# os_-_5V0_converter.net
KiCad netlist of a schematic drawn in EAGLE
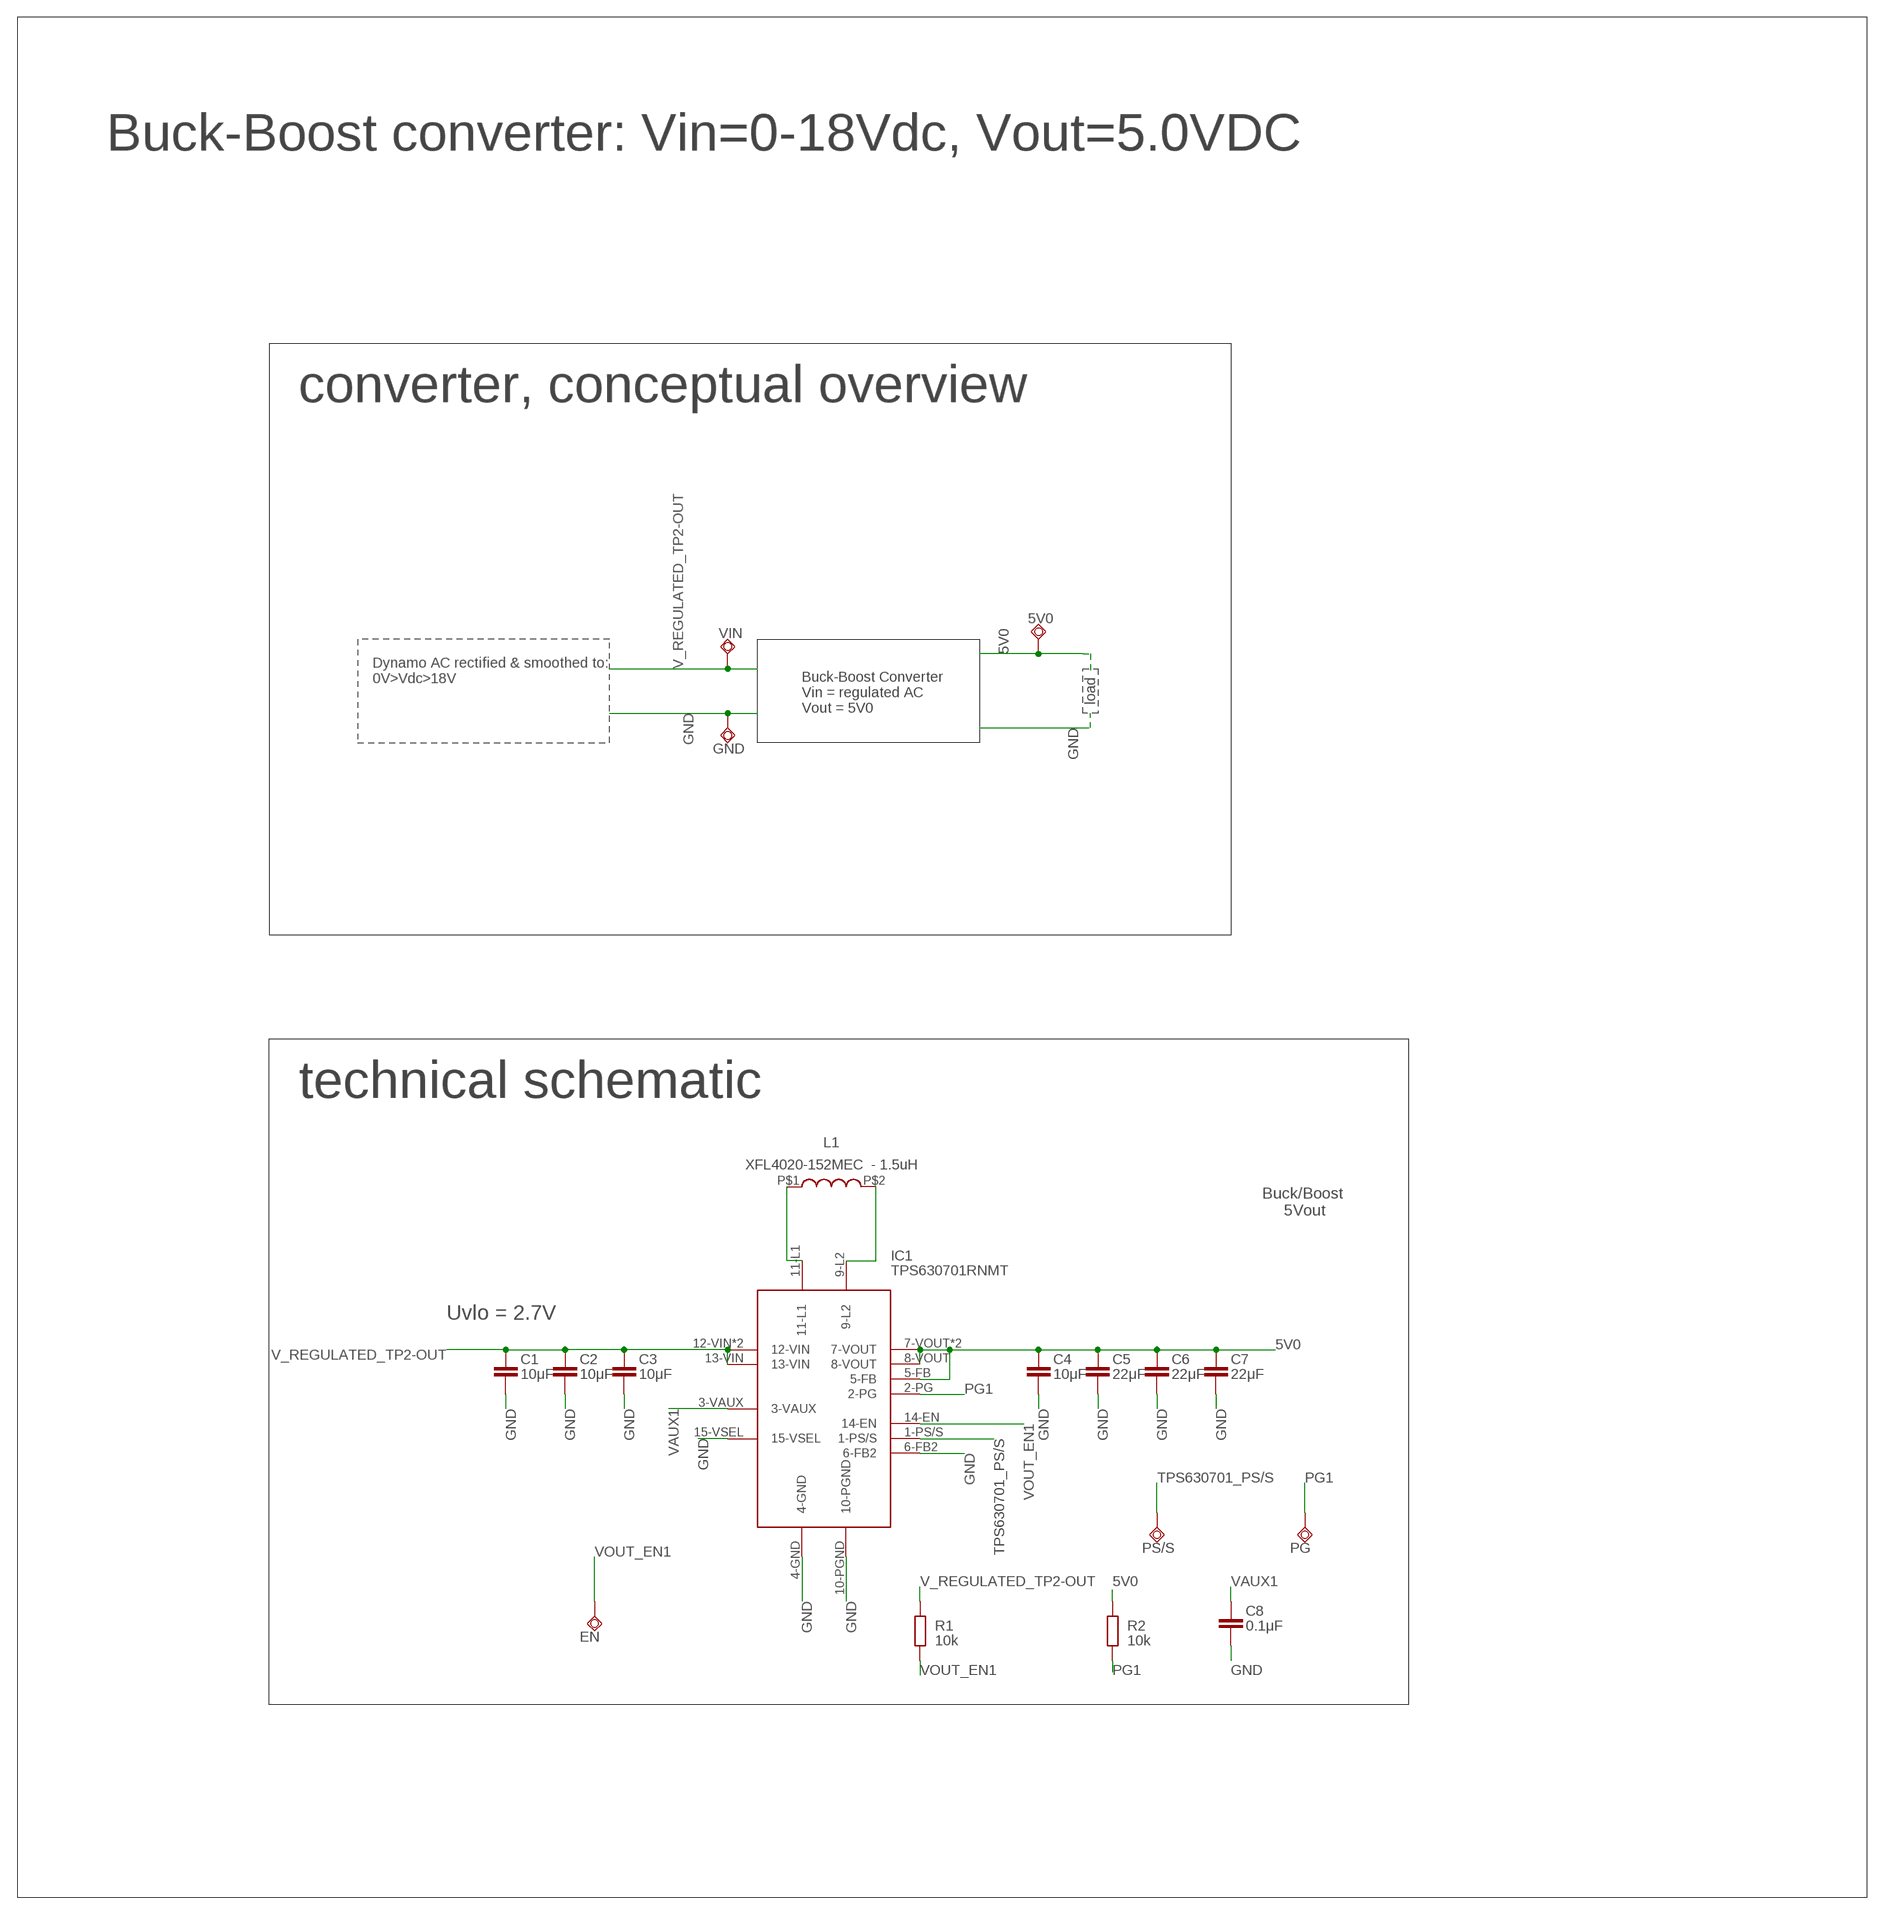
[diagram p0: schematic, sheet 1]

(export (version "E")
  (design (tool "Eeschema 10.0.6"))
  (components
    (comp (ref "5V0")
      (value "TPSQPAD1-13")
      (footprint "eagle-import:P1-13")
      (libsource (lib "eagle-import") (part "TPSQPAD1-13"))
    )
    (comp (ref "C1")
      (value "10μF")
      (footprint "eagle-import:C0805")
      (libsource (lib "eagle-import") (part "C-EUC0805"))
    )
    (comp (ref "C2")
      (value "10μF")
      (footprint "eagle-import:C0805")
      (libsource (lib "eagle-import") (part "C-EUC0805"))
    )
    (comp (ref "C3")
      (value "10μF")
      (footprint "eagle-import:C0603")
      (libsource (lib "eagle-import") (part "C-EUC0603"))
    )
    (comp (ref "C4")
      (value "10μF")
      (footprint "eagle-import:C0603")
      (libsource (lib "eagle-import") (part "C-EUC0603"))
    )
    (comp (ref "C5")
      (value "22μF")
      (footprint "eagle-import:C0805")
      (libsource (lib "eagle-import") (part "C-EUC0805"))
    )
    (comp (ref "C6")
      (value "22μF")
      (footprint "eagle-import:C0805")
      (libsource (lib "eagle-import") (part "C-EUC0805"))
    )
    (comp (ref "C7")
      (value "22μF")
      (footprint "eagle-import:C0805")
      (libsource (lib "eagle-import") (part "C-EUC0805"))
    )
    (comp (ref "C8")
      (value "0.1μF")
      (footprint "eagle-import:C0402")
      (libsource (lib "eagle-import") (part "C-EUC0402"))
    )
    (comp (ref "EN")
      (value "TPSQTP13R")
      (footprint "eagle-import:TP13R")
      (libsource (lib "eagle-import") (part "TPSQTP13R"))
    )
    (comp (ref "GND")
      (value "TPSQPAD1-13")
      (footprint "eagle-import:P1-13")
      (libsource (lib "eagle-import") (part "TPSQPAD1-13"))
    )
    (comp (ref "IC1")
      (value "TPS630701RNMT")
      (footprint "eagle-import:VQFN")
      (libsource (lib "eagle-import") (part "TPS630701"))
    )
    (comp (ref "L1")
      (value "XFL4020-152MEC - 1.5uH")
      (footprint "eagle-import:SMD")
      (libsource (lib "eagle-import") (part "XFL4020-152MEC"))
    )
    (comp (ref "PG")
      (value "TPSQTP13R")
      (footprint "eagle-import:TP13R")
      (libsource (lib "eagle-import") (part "TPSQTP13R"))
    )
    (comp (ref "PS/S")
      (value "TPSQTP13R")
      (footprint "eagle-import:TP13R")
      (libsource (lib "eagle-import") (part "TPSQTP13R"))
    )
    (comp (ref "R1")
      (value "10k")
      (footprint "eagle-import:R0402")
      (libsource (lib "eagle-import") (part "R-EU_R0402"))
    )
    (comp (ref "R2")
      (value "10k")
      (footprint "eagle-import:R0402")
      (libsource (lib "eagle-import") (part "R-EU_R0402"))
    )
    (comp (ref "VIN")
      (value "TPSQPAD1-13")
      (footprint "eagle-import:P1-13")
      (libsource (lib "eagle-import") (part "TPSQPAD1-13"))
    )
  )
  (nets
    (net (code "1") (name "/5V0") (class "Default")
      (node (ref "5V0") (pin "TP") (pinfunction "TP_TP") (pintype "input"))
      (node (ref "C4") (pin "1") (pinfunction "1_1") (pintype "passive"))
      (node (ref "C5") (pin "1") (pinfunction "1_1") (pintype "passive"))
      (node (ref "C6") (pin "1") (pinfunction "1_1") (pintype "passive"))
      (node (ref "C7") (pin "1") (pinfunction "1_1") (pintype "passive"))
      (node (ref "IC1") (pin "5-FB") (pinfunction "5-FB_5-FB") (pintype "bidirectional"))
      (node (ref "IC1") (pin "7-VOUT") (pinfunction "7-VOUT_7-VOUT") (pintype "bidirectional"))
      (node (ref "IC1") (pin "8-VOUT") (pinfunction "8-VOUT_8-VOUT") (pintype "bidirectional"))
      (node (ref "IC1") (pin "VOUT") (pinfunction "7-VOUT_VOUT") (pintype "bidirectional"))
      (node (ref "R2") (pin "2") (pinfunction "2_2") (pintype "passive"))
    )
    (net (code "2") (name "/GND") (class "Default")
      (node (ref "C1") (pin "2") (pinfunction "2_2") (pintype "passive"))
      (node (ref "C2") (pin "2") (pinfunction "2_2") (pintype "passive"))
      (node (ref "C3") (pin "2") (pinfunction "2_2") (pintype "passive"))
      (node (ref "C4") (pin "2") (pinfunction "2_2") (pintype "passive"))
      (node (ref "C5") (pin "2") (pinfunction "2_2") (pintype "passive"))
      (node (ref "C6") (pin "2") (pinfunction "2_2") (pintype "passive"))
      (node (ref "C7") (pin "2") (pinfunction "2_2") (pintype "passive"))
      (node (ref "C8") (pin "2") (pinfunction "2_2") (pintype "passive"))
      (node (ref "GND") (pin "TP") (pinfunction "TP_TP") (pintype "input"))
      (node (ref "IC1") (pin "10-PGND") (pinfunction "10-PGND_10-PGND") (pintype "bidirectional"))
      (node (ref "IC1") (pin "15-VSEL") (pinfunction "15-VSEL_15-VSEL") (pintype "bidirectional"))
      (node (ref "IC1") (pin "4-GND") (pinfunction "4-GND_4-GND") (pintype "bidirectional"))
      (node (ref "IC1") (pin "6-FB2") (pinfunction "6-FB2_6-FB2") (pintype "bidirectional"))
    )
    (net (code "3") (name "/PG1") (class "Default")
      (node (ref "IC1") (pin "2-PG") (pinfunction "2-PG_2-PG") (pintype "bidirectional"))
      (node (ref "PG") (pin "TP") (pinfunction "TP_TP") (pintype "input"))
      (node (ref "R2") (pin "1") (pinfunction "1_1") (pintype "passive"))
    )
    (net (code "4") (name "/TPS630701_PS{slash}S") (class "Default")
      (node (ref "IC1") (pin "1-PS/S") (pinfunction "1-PS/S_1-PS/S") (pintype "bidirectional"))
      (node (ref "PS/S") (pin "TP") (pinfunction "TP_TP") (pintype "input"))
    )
    (net (code "5") (name "/VAUX1") (class "Default")
      (node (ref "C8") (pin "1") (pinfunction "1_1") (pintype "passive"))
      (node (ref "IC1") (pin "3-VAUX") (pinfunction "3-VAUX_3-VAUX") (pintype "bidirectional"))
    )
    (net (code "6") (name "/VOUT_EN1") (class "Default")
      (node (ref "EN") (pin "TP") (pinfunction "TP_TP") (pintype "input"))
      (node (ref "IC1") (pin "14-EN") (pinfunction "14-EN_14-EN") (pintype "bidirectional"))
      (node (ref "R1") (pin "1") (pinfunction "1_1") (pintype "passive"))
    )
    (net (code "7") (name "/V_REGULATED_TP2-OUT") (class "Default")
      (node (ref "C1") (pin "1") (pinfunction "1_1") (pintype "passive"))
      (node (ref "C2") (pin "1") (pinfunction "1_1") (pintype "passive"))
      (node (ref "C3") (pin "1") (pinfunction "1_1") (pintype "passive"))
      (node (ref "IC1") (pin "12-VIN") (pinfunction "12-VIN_12-VIN") (pintype "bidirectional"))
      (node (ref "IC1") (pin "13-VIN") (pinfunction "13-VIN_13-VIN") (pintype "bidirectional"))
      (node (ref "IC1") (pin "VIN") (pinfunction "12-VIN_VIN") (pintype "bidirectional"))
      (node (ref "R1") (pin "2") (pinfunction "2_2") (pintype "passive"))
      (node (ref "VIN") (pin "TP") (pinfunction "TP_TP") (pintype "input"))
    )
    (net (code "8") (name "Net-(IC1-Pad9-L2)") (class "Default")
      (node (ref "IC1") (pin "9-L2") (pinfunction "9-L2_9-L2") (pintype "bidirectional"))
      (node (ref "L1") (pin "P$2") (pinfunction "P$2_P$2") (pintype "bidirectional"))
    )
    (net (code "9") (name "Net-(IC1-Pad11-L1)") (class "Default")
      (node (ref "IC1") (pin "11-L1") (pinfunction "11-L1_11-L1") (pintype "bidirectional"))
      (node (ref "L1") (pin "P$1") (pinfunction "P$1_P$1") (pintype "bidirectional"))
    )
  )
)
